# PIC.net
KiCad netlist of a schematic drawn in Altium Designer
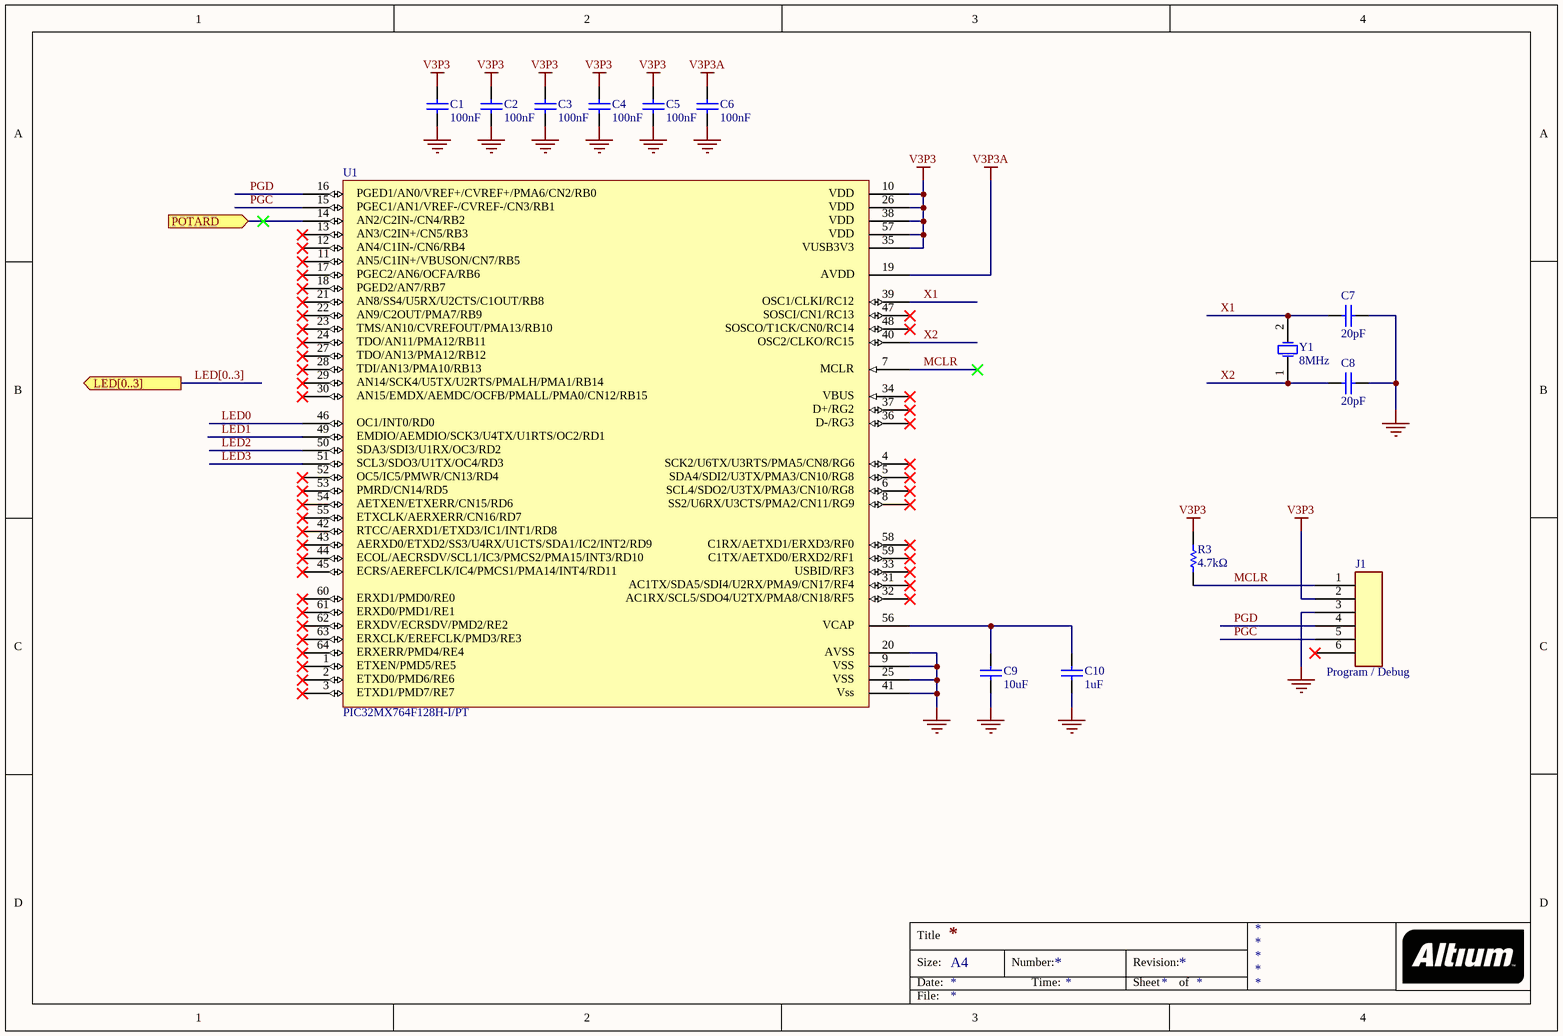
[diagram p0: PIC.SchDoc]

(export (version "E")
  (design (tool "Eeschema 10.0.6"))
  (components
    (comp (ref "C1")
      (value "100nF")
      (footprint "CAPC1608N")
      (description "Capacitor")
      (fields (field (name "PUBLISHER") "Altium Limited"))
      (libsource (lib "Miscellaneous Devices") (part "Cap"))
    )
    (comp (ref "C2")
      (value "100nF")
      (footprint "CAPC1608N")
      (description "Capacitor")
      (fields (field (name "PUBLISHER") "Altium Limited"))
      (libsource (lib "Miscellaneous Devices") (part "Cap"))
    )
    (comp (ref "C3")
      (value "100nF")
      (footprint "CAPC1608N")
      (description "Capacitor")
      (fields (field (name "PUBLISHER") "Altium Limited"))
      (libsource (lib "Miscellaneous Devices") (part "Cap"))
    )
    (comp (ref "C4")
      (value "100nF")
      (footprint "CAPC1608N")
      (description "Capacitor")
      (fields (field (name "PUBLISHER") "Altium Limited"))
      (libsource (lib "Miscellaneous Devices") (part "Cap"))
    )
    (comp (ref "C5")
      (value "100nF")
      (footprint "CAPC1608N")
      (description "Capacitor")
      (fields (field (name "PUBLISHER") "Altium Limited"))
      (libsource (lib "Miscellaneous Devices") (part "Cap"))
    )
    (comp (ref "C6")
      (value "100nF")
      (footprint "CAPC1608N")
      (description "Capacitor")
      (fields (field (name "PUBLISHER") "Altium Limited"))
      (libsource (lib "Miscellaneous Devices") (part "Cap"))
    )
    (comp (ref "C7")
      (value "20pF")
      (footprint "CAPC1005N")
      (description "Capacitor")
      (fields (field (name "PUBLISHER") "Altium Limited"))
      (libsource (lib "Miscellaneous Devices") (part "Cap"))
    )
    (comp (ref "C8")
      (value "20pF")
      (footprint "CAPC1005N")
      (description "Capacitor")
      (fields (field (name "PUBLISHER") "Altium Limited"))
      (libsource (lib "Miscellaneous Devices") (part "Cap"))
    )
    (comp (ref "C9")
      (value "10uF")
      (footprint "CAPC2012N")
      (description "Capacitor")
      (fields (field (name "PUBLISHER") "Altium Limited"))
      (libsource (lib "Miscellaneous Devices") (part "Cap"))
    )
    (comp (ref "C10")
      (value "1uF")
      (footprint "CAPC1608N")
      (description "Capacitor")
      (fields (field (name "PUBLISHER") "Altium Limited"))
      (libsource (lib "Miscellaneous Devices") (part "Cap"))
    )
    (comp (ref "J1") (value "Program / Debug") (libsource (lib "PIC") (part "CON6")))
    (comp (ref "R3")
      (value "4.7kΩ")
      (footprint "RESC1608N")
      (description "Resistor")
      (fields (field (name "PUBLISHER") "Altium Limited"))
      (libsource (lib "Miscellaneous Devices") (part "Res1"))
    )
    (comp (ref "U1")
      (value "PIC32MX764F128H-I/PT")
      (description "PIC32MX764F128H")
      (libsource (lib "PIC") (part "PIC32MX764F128H-I/PT"))
    )
    (comp (ref "Y1")
      (value "8MHz")
      (footprint "PCBComponent_1")
      (description "Crystal Oscillator")
      (fields (field (name "PUBLISHER") "Altium Limited"))
      (libsource (lib "Miscellaneous Devices") (part "XTAL"))
    )
  )
  (nets
    (net (code "1") (name "/LED0") (class "Default")
      (node (ref "U1") (pin "46") (pinfunction "46_46") (pintype "bidirectional"))
    )
    (net (code "2") (name "/LED1") (class "Default")
      (node (ref "U1") (pin "49") (pinfunction "49_49") (pintype "bidirectional"))
    )
    (net (code "3") (name "/LED2") (class "Default")
      (node (ref "U1") (pin "50") (pinfunction "50_50") (pintype "bidirectional"))
    )
    (net (code "4") (name "/LED3") (class "Default")
      (node (ref "U1") (pin "51") (pinfunction "51_51") (pintype "bidirectional"))
    )
    (net (code "6") (name "/MCLR") (class "Default")
      (node (ref "J1") (pin "1") (pinfunction "1_1") (pintype "power_in"))
      (node (ref "R3") (pin "1") (pinfunction "1_1") (pintype "passive"))
      (node (ref "U1") (pin "7") (pinfunction "7_7") (pintype "input"))
    )
    (net (code "7") (name "/PGC") (class "Default")
      (node (ref "J1") (pin "5") (pinfunction "5_5") (pintype "power_in"))
      (node (ref "U1") (pin "15") (pinfunction "15_15") (pintype "bidirectional"))
    )
    (net (code "8") (name "/PGD") (class "Default")
      (node (ref "J1") (pin "4") (pinfunction "4_4") (pintype "power_in"))
      (node (ref "U1") (pin "16") (pinfunction "16_16") (pintype "bidirectional"))
    )
    (net (code "9") (name "/POTARD") (class "Default")
      (node (ref "U1") (pin "14") (pinfunction "14_14") (pintype "bidirectional+no_connect"))
    )
    (net (code "10") (name "/X1") (class "Default")
      (node (ref "C7") (pin "1") (pinfunction "1_1") (pintype "passive"))
      (node (ref "U1") (pin "39") (pinfunction "39_39") (pintype "bidirectional"))
      (node (ref "Y1") (pin "2") (pinfunction "OSC2_2") (pintype "passive"))
    )
    (net (code "11") (name "/X2") (class "Default")
      (node (ref "C8") (pin "1") (pinfunction "1_1") (pintype "passive"))
      (node (ref "U1") (pin "40") (pinfunction "40_40") (pintype "bidirectional"))
      (node (ref "Y1") (pin "1") (pinfunction "OSC1_1") (pintype "passive"))
    )
    (net (code "12") (name "GND") (class "Default")
      (node (ref "C1") (pin "1") (pinfunction "1_1") (pintype "passive"))
      (node (ref "C10") (pin "1") (pinfunction "1_1") (pintype "passive"))
      (node (ref "C2") (pin "1") (pinfunction "1_1") (pintype "passive"))
      (node (ref "C3") (pin "1") (pinfunction "1_1") (pintype "passive"))
      (node (ref "C4") (pin "1") (pinfunction "1_1") (pintype "passive"))
      (node (ref "C5") (pin "1") (pinfunction "1_1") (pintype "passive"))
      (node (ref "C6") (pin "1") (pinfunction "1_1") (pintype "passive"))
      (node (ref "C7") (pin "2") (pinfunction "2_2") (pintype "passive"))
      (node (ref "C8") (pin "2") (pinfunction "2_2") (pintype "passive"))
      (node (ref "C9") (pin "1") (pinfunction "1_1") (pintype "passive"))
      (node (ref "J1") (pin "3") (pinfunction "3_3") (pintype "power_in"))
      (node (ref "U1") (pin "20") (pinfunction "20_20") (pintype "power_in"))
      (node (ref "U1") (pin "25") (pinfunction "25_25") (pintype "power_in"))
      (node (ref "U1") (pin "41") (pinfunction "41_41") (pintype "power_in"))
      (node (ref "U1") (pin "9") (pinfunction "9_9") (pintype "power_in"))
    )
    (net (code "13") (name "Net-(C10-Pad2)") (class "Default")
      (node (ref "C10") (pin "2") (pinfunction "2_2") (pintype "passive"))
      (node (ref "C9") (pin "2") (pinfunction "2_2") (pintype "passive"))
      (node (ref "U1") (pin "56") (pinfunction "56_56") (pintype "power_in"))
    )
    (net (code "14") (name "V3P3") (class "Default")
      (node (ref "C1") (pin "2") (pinfunction "2_2") (pintype "passive"))
      (node (ref "C2") (pin "2") (pinfunction "2_2") (pintype "passive"))
      (node (ref "C3") (pin "2") (pinfunction "2_2") (pintype "passive"))
      (node (ref "C4") (pin "2") (pinfunction "2_2") (pintype "passive"))
      (node (ref "C5") (pin "2") (pinfunction "2_2") (pintype "passive"))
      (node (ref "J1") (pin "2") (pinfunction "2_2") (pintype "power_in"))
      (node (ref "R3") (pin "2") (pinfunction "2_2") (pintype "passive"))
      (node (ref "U1") (pin "10") (pinfunction "10_10") (pintype "power_in"))
      (node (ref "U1") (pin "26") (pinfunction "26_26") (pintype "power_in"))
      (node (ref "U1") (pin "35") (pinfunction "35_35") (pintype "power_in"))
      (node (ref "U1") (pin "38") (pinfunction "38_38") (pintype "power_in"))
      (node (ref "U1") (pin "57") (pinfunction "57_57") (pintype "power_in"))
    )
    (net (code "15") (name "V3P3A") (class "Default")
      (node (ref "C6") (pin "2") (pinfunction "2_2") (pintype "passive"))
      (node (ref "U1") (pin "19") (pinfunction "19_19") (pintype "power_in"))
    )
    (net (code "16") (name "unconnected-(J1-Pad6)") (class "Default")
      (node (ref "J1") (pin "6") (pinfunction "6_6") (pintype "power_in+no_connect"))
    )
    (net (code "17") (name "unconnected-(U1-Pad1)") (class "Default")
      (node (ref "U1") (pin "1") (pinfunction "1_1") (pintype "bidirectional+no_connect"))
    )
    (net (code "18") (name "unconnected-(U1-Pad2)") (class "Default")
      (node (ref "U1") (pin "2") (pinfunction "2_2") (pintype "bidirectional+no_connect"))
    )
    (net (code "19") (name "unconnected-(U1-Pad3)") (class "Default")
      (node (ref "U1") (pin "3") (pinfunction "3_3") (pintype "bidirectional+no_connect"))
    )
    (net (code "20") (name "unconnected-(U1-Pad4)") (class "Default")
      (node (ref "U1") (pin "4") (pinfunction "4_4") (pintype "bidirectional+no_connect"))
    )
    (net (code "21") (name "unconnected-(U1-Pad5)") (class "Default")
      (node (ref "U1") (pin "5") (pinfunction "5_5") (pintype "bidirectional+no_connect"))
    )
    (net (code "22") (name "unconnected-(U1-Pad6)") (class "Default")
      (node (ref "U1") (pin "6") (pinfunction "6_6") (pintype "bidirectional+no_connect"))
    )
    (net (code "23") (name "unconnected-(U1-Pad8)") (class "Default")
      (node (ref "U1") (pin "8") (pinfunction "8_8") (pintype "bidirectional+no_connect"))
    )
    (net (code "24") (name "unconnected-(U1-Pad11)") (class "Default")
      (node (ref "U1") (pin "11") (pinfunction "11_11") (pintype "bidirectional+no_connect"))
    )
    (net (code "25") (name "unconnected-(U1-Pad12)") (class "Default")
      (node (ref "U1") (pin "12") (pinfunction "12_12") (pintype "bidirectional+no_connect"))
    )
    (net (code "26") (name "unconnected-(U1-Pad13)") (class "Default")
      (node (ref "U1") (pin "13") (pinfunction "13_13") (pintype "bidirectional+no_connect"))
    )
    (net (code "27") (name "unconnected-(U1-Pad17)") (class "Default")
      (node (ref "U1") (pin "17") (pinfunction "17_17") (pintype "bidirectional+no_connect"))
    )
    (net (code "28") (name "unconnected-(U1-Pad18)") (class "Default")
      (node (ref "U1") (pin "18") (pinfunction "18_18") (pintype "bidirectional+no_connect"))
    )
    (net (code "29") (name "unconnected-(U1-Pad21)") (class "Default")
      (node (ref "U1") (pin "21") (pinfunction "21_21") (pintype "bidirectional+no_connect"))
    )
    (net (code "30") (name "unconnected-(U1-Pad22)") (class "Default")
      (node (ref "U1") (pin "22") (pinfunction "22_22") (pintype "bidirectional+no_connect"))
    )
    (net (code "31") (name "unconnected-(U1-Pad23)") (class "Default")
      (node (ref "U1") (pin "23") (pinfunction "23_23") (pintype "bidirectional+no_connect"))
    )
    (net (code "32") (name "unconnected-(U1-Pad24)") (class "Default")
      (node (ref "U1") (pin "24") (pinfunction "24_24") (pintype "bidirectional+no_connect"))
    )
    (net (code "33") (name "unconnected-(U1-Pad27)") (class "Default")
      (node (ref "U1") (pin "27") (pinfunction "27_27") (pintype "bidirectional+no_connect"))
    )
    (net (code "34") (name "unconnected-(U1-Pad28)") (class "Default")
      (node (ref "U1") (pin "28") (pinfunction "28_28") (pintype "bidirectional+no_connect"))
    )
    (net (code "35") (name "unconnected-(U1-Pad29)") (class "Default")
      (node (ref "U1") (pin "29") (pinfunction "29_29") (pintype "bidirectional+no_connect"))
    )
    (net (code "36") (name "unconnected-(U1-Pad30)") (class "Default")
      (node (ref "U1") (pin "30") (pinfunction "30_30") (pintype "bidirectional+no_connect"))
    )
    (net (code "37") (name "unconnected-(U1-Pad31)") (class "Default")
      (node (ref "U1") (pin "31") (pinfunction "31_31") (pintype "bidirectional+no_connect"))
    )
    (net (code "38") (name "unconnected-(U1-Pad32)") (class "Default")
      (node (ref "U1") (pin "32") (pinfunction "32_32") (pintype "bidirectional+no_connect"))
    )
    (net (code "39") (name "unconnected-(U1-Pad33)") (class "Default")
      (node (ref "U1") (pin "33") (pinfunction "33_33") (pintype "bidirectional+no_connect"))
    )
    (net (code "40") (name "unconnected-(U1-Pad34)") (class "Default")
      (node (ref "U1") (pin "34") (pinfunction "34_34") (pintype "input+no_connect"))
    )
    (net (code "41") (name "unconnected-(U1-Pad36)") (class "Default")
      (node (ref "U1") (pin "36") (pinfunction "36_36") (pintype "bidirectional+no_connect"))
    )
    (net (code "42") (name "unconnected-(U1-Pad37)") (class "Default")
      (node (ref "U1") (pin "37") (pinfunction "37_37") (pintype "bidirectional+no_connect"))
    )
    (net (code "43") (name "unconnected-(U1-Pad42)") (class "Default")
      (node (ref "U1") (pin "42") (pinfunction "42_42") (pintype "bidirectional+no_connect"))
    )
    (net (code "44") (name "unconnected-(U1-Pad43)") (class "Default")
      (node (ref "U1") (pin "43") (pinfunction "43_43") (pintype "bidirectional+no_connect"))
    )
    (net (code "45") (name "unconnected-(U1-Pad44)") (class "Default")
      (node (ref "U1") (pin "44") (pinfunction "44_44") (pintype "bidirectional+no_connect"))
    )
    (net (code "46") (name "unconnected-(U1-Pad45)") (class "Default")
      (node (ref "U1") (pin "45") (pinfunction "45_45") (pintype "bidirectional+no_connect"))
    )
    (net (code "47") (name "unconnected-(U1-Pad47)") (class "Default")
      (node (ref "U1") (pin "47") (pinfunction "47_47") (pintype "bidirectional+no_connect"))
    )
    (net (code "48") (name "unconnected-(U1-Pad48)") (class "Default")
      (node (ref "U1") (pin "48") (pinfunction "48_48") (pintype "bidirectional+no_connect"))
    )
    (net (code "49") (name "unconnected-(U1-Pad52)") (class "Default")
      (node (ref "U1") (pin "52") (pinfunction "52_52") (pintype "bidirectional+no_connect"))
    )
    (net (code "50") (name "unconnected-(U1-Pad53)") (class "Default")
      (node (ref "U1") (pin "53") (pinfunction "53_53") (pintype "bidirectional+no_connect"))
    )
    (net (code "51") (name "unconnected-(U1-Pad54)") (class "Default")
      (node (ref "U1") (pin "54") (pinfunction "54_54") (pintype "bidirectional+no_connect"))
    )
    (net (code "52") (name "unconnected-(U1-Pad55)") (class "Default")
      (node (ref "U1") (pin "55") (pinfunction "55_55") (pintype "bidirectional+no_connect"))
    )
    (net (code "53") (name "unconnected-(U1-Pad58)") (class "Default")
      (node (ref "U1") (pin "58") (pinfunction "58_58") (pintype "bidirectional+no_connect"))
    )
    (net (code "54") (name "unconnected-(U1-Pad59)") (class "Default")
      (node (ref "U1") (pin "59") (pinfunction "59_59") (pintype "bidirectional+no_connect"))
    )
    (net (code "55") (name "unconnected-(U1-Pad60)") (class "Default")
      (node (ref "U1") (pin "60") (pinfunction "60_60") (pintype "bidirectional+no_connect"))
    )
    (net (code "56") (name "unconnected-(U1-Pad61)") (class "Default")
      (node (ref "U1") (pin "61") (pinfunction "61_61") (pintype "bidirectional+no_connect"))
    )
    (net (code "57") (name "unconnected-(U1-Pad62)") (class "Default")
      (node (ref "U1") (pin "62") (pinfunction "62_62") (pintype "bidirectional+no_connect"))
    )
    (net (code "58") (name "unconnected-(U1-Pad63)") (class "Default")
      (node (ref "U1") (pin "63") (pinfunction "63_63") (pintype "bidirectional+no_connect"))
    )
    (net (code "59") (name "unconnected-(U1-Pad64)") (class "Default")
      (node (ref "U1") (pin "64") (pinfunction "64_64") (pintype "bidirectional+no_connect"))
    )
  )
)
